# connector-top-j4-1.net
KiCad netlist of a schematic drawn in Altium Designer
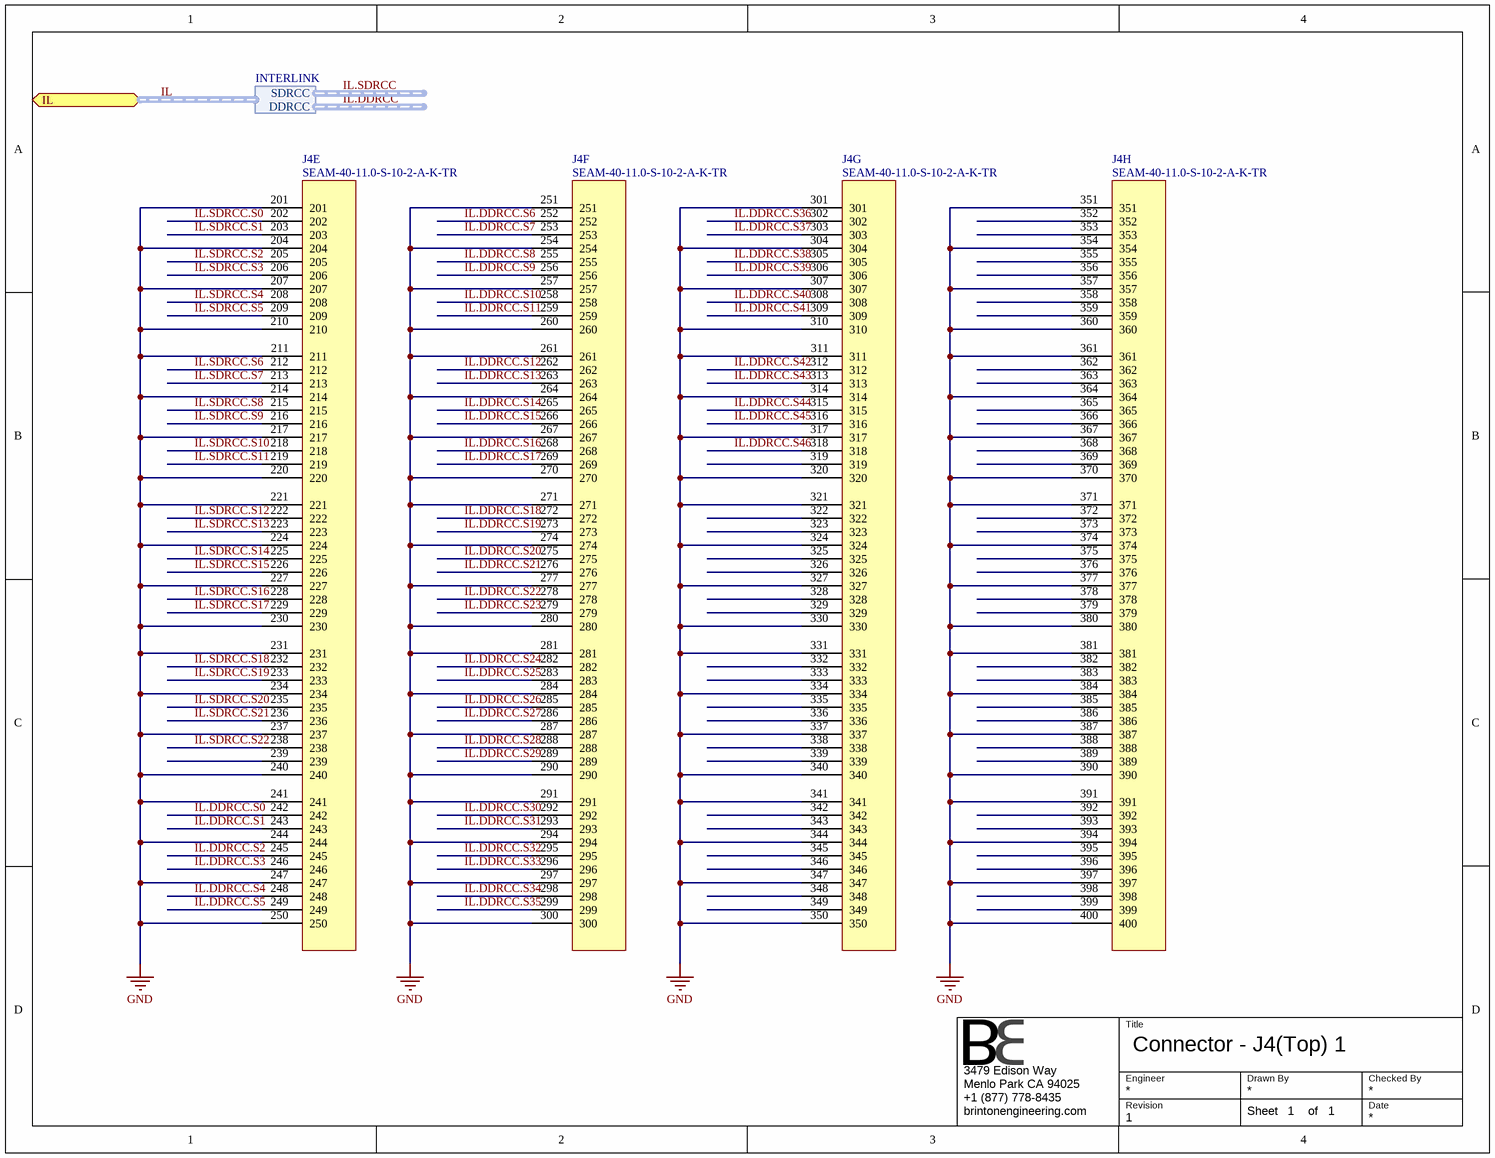
[diagram p0: connector-top-j4-1.SchDoc]

(export (version "E")
  (design (tool "Eeschema 10.0.6"))
  (components
    (comp (ref "J4")
      (value "SEAM-40-11.0-S-10-2-A-K-TR")
      (footprint "samtec:SEAM-40-11.0-S-10-2-A-K-TR")
      (description "Terminal Array Assembly, Surface Mount, 0.050\" Pitch, 400 Pins")
      (fields (field (name "MANUFACTURER") "Samtec"))
      (libsource (lib "samtec") (part "SEAM-40-11.0-S-10-2-A-K-TR"))
    )
  )
  (nets
    (net (code "3") (name "/IL.DDRCC.S0") (class "Default")
      (node (ref "J4") (pin "242") (pinfunction "242_242") (pintype "passive"))
    )
    (net (code "4") (name "/IL.DDRCC.S1") (class "Default")
      (node (ref "J4") (pin "243") (pinfunction "243_243") (pintype "passive"))
    )
    (net (code "5") (name "/IL.DDRCC.S2") (class "Default")
      (node (ref "J4") (pin "245") (pinfunction "245_245") (pintype "passive"))
    )
    (net (code "6") (name "/IL.DDRCC.S3") (class "Default")
      (node (ref "J4") (pin "246") (pinfunction "246_246") (pintype "passive"))
    )
    (net (code "7") (name "/IL.DDRCC.S4") (class "Default")
      (node (ref "J4") (pin "248") (pinfunction "248_248") (pintype "passive"))
    )
    (net (code "8") (name "/IL.DDRCC.S5") (class "Default")
      (node (ref "J4") (pin "249") (pinfunction "249_249") (pintype "passive"))
    )
    (net (code "9") (name "/IL.DDRCC.S6") (class "Default")
      (node (ref "J4") (pin "252") (pinfunction "252_252") (pintype "passive"))
    )
    (net (code "10") (name "/IL.DDRCC.S7") (class "Default")
      (node (ref "J4") (pin "253") (pinfunction "253_253") (pintype "passive"))
    )
    (net (code "11") (name "/IL.DDRCC.S8") (class "Default")
      (node (ref "J4") (pin "255") (pinfunction "255_255") (pintype "passive"))
    )
    (net (code "12") (name "/IL.DDRCC.S9") (class "Default")
      (node (ref "J4") (pin "256") (pinfunction "256_256") (pintype "passive"))
    )
    (net (code "13") (name "/IL.DDRCC.S10") (class "Default")
      (node (ref "J4") (pin "258") (pinfunction "258_258") (pintype "passive"))
    )
    (net (code "14") (name "/IL.DDRCC.S11") (class "Default")
      (node (ref "J4") (pin "259") (pinfunction "259_259") (pintype "passive"))
    )
    (net (code "15") (name "/IL.DDRCC.S12") (class "Default")
      (node (ref "J4") (pin "262") (pinfunction "262_262") (pintype "passive"))
    )
    (net (code "16") (name "/IL.DDRCC.S13") (class "Default")
      (node (ref "J4") (pin "263") (pinfunction "263_263") (pintype "passive"))
    )
    (net (code "17") (name "/IL.DDRCC.S14") (class "Default")
      (node (ref "J4") (pin "265") (pinfunction "265_265") (pintype "passive"))
    )
    (net (code "18") (name "/IL.DDRCC.S15") (class "Default")
      (node (ref "J4") (pin "266") (pinfunction "266_266") (pintype "passive"))
    )
    (net (code "19") (name "/IL.DDRCC.S16") (class "Default")
      (node (ref "J4") (pin "268") (pinfunction "268_268") (pintype "passive"))
    )
    (net (code "20") (name "/IL.DDRCC.S17") (class "Default")
      (node (ref "J4") (pin "269") (pinfunction "269_269") (pintype "passive"))
    )
    (net (code "21") (name "/IL.DDRCC.S18") (class "Default")
      (node (ref "J4") (pin "272") (pinfunction "272_272") (pintype "passive"))
    )
    (net (code "22") (name "/IL.DDRCC.S19") (class "Default")
      (node (ref "J4") (pin "273") (pinfunction "273_273") (pintype "passive"))
    )
    (net (code "23") (name "/IL.DDRCC.S20") (class "Default")
      (node (ref "J4") (pin "275") (pinfunction "275_275") (pintype "passive"))
    )
    (net (code "24") (name "/IL.DDRCC.S21") (class "Default")
      (node (ref "J4") (pin "276") (pinfunction "276_276") (pintype "passive"))
    )
    (net (code "25") (name "/IL.DDRCC.S22") (class "Default")
      (node (ref "J4") (pin "278") (pinfunction "278_278") (pintype "passive"))
    )
    (net (code "26") (name "/IL.DDRCC.S23") (class "Default")
      (node (ref "J4") (pin "279") (pinfunction "279_279") (pintype "passive"))
    )
    (net (code "27") (name "/IL.DDRCC.S24") (class "Default")
      (node (ref "J4") (pin "282") (pinfunction "282_282") (pintype "passive"))
    )
    (net (code "28") (name "/IL.DDRCC.S25") (class "Default")
      (node (ref "J4") (pin "283") (pinfunction "283_283") (pintype "passive"))
    )
    (net (code "29") (name "/IL.DDRCC.S26") (class "Default")
      (node (ref "J4") (pin "285") (pinfunction "285_285") (pintype "passive"))
    )
    (net (code "30") (name "/IL.DDRCC.S27") (class "Default")
      (node (ref "J4") (pin "286") (pinfunction "286_286") (pintype "passive"))
    )
    (net (code "31") (name "/IL.DDRCC.S28") (class "Default")
      (node (ref "J4") (pin "288") (pinfunction "288_288") (pintype "passive"))
    )
    (net (code "32") (name "/IL.DDRCC.S29") (class "Default")
      (node (ref "J4") (pin "289") (pinfunction "289_289") (pintype "passive"))
    )
    (net (code "33") (name "/IL.DDRCC.S30") (class "Default")
      (node (ref "J4") (pin "292") (pinfunction "292_292") (pintype "passive"))
    )
    (net (code "34") (name "/IL.DDRCC.S31") (class "Default")
      (node (ref "J4") (pin "293") (pinfunction "293_293") (pintype "passive"))
    )
    (net (code "35") (name "/IL.DDRCC.S32") (class "Default")
      (node (ref "J4") (pin "295") (pinfunction "295_295") (pintype "passive"))
    )
    (net (code "36") (name "/IL.DDRCC.S33") (class "Default")
      (node (ref "J4") (pin "296") (pinfunction "296_296") (pintype "passive"))
    )
    (net (code "37") (name "/IL.DDRCC.S34") (class "Default")
      (node (ref "J4") (pin "298") (pinfunction "298_298") (pintype "passive"))
    )
    (net (code "38") (name "/IL.DDRCC.S35") (class "Default")
      (node (ref "J4") (pin "299") (pinfunction "299_299") (pintype "passive"))
    )
    (net (code "39") (name "/IL.DDRCC.S36") (class "Default")
      (node (ref "J4") (pin "302") (pinfunction "302_302") (pintype "passive"))
    )
    (net (code "40") (name "/IL.DDRCC.S37") (class "Default")
      (node (ref "J4") (pin "303") (pinfunction "303_303") (pintype "passive"))
    )
    (net (code "41") (name "/IL.DDRCC.S38") (class "Default")
      (node (ref "J4") (pin "305") (pinfunction "305_305") (pintype "passive"))
    )
    (net (code "42") (name "/IL.DDRCC.S39") (class "Default")
      (node (ref "J4") (pin "306") (pinfunction "306_306") (pintype "passive"))
    )
    (net (code "43") (name "/IL.DDRCC.S40") (class "Default")
      (node (ref "J4") (pin "308") (pinfunction "308_308") (pintype "passive"))
    )
    (net (code "44") (name "/IL.DDRCC.S41") (class "Default")
      (node (ref "J4") (pin "309") (pinfunction "309_309") (pintype "passive"))
    )
    (net (code "45") (name "/IL.DDRCC.S42") (class "Default")
      (node (ref "J4") (pin "312") (pinfunction "312_312") (pintype "passive"))
    )
    (net (code "46") (name "/IL.DDRCC.S43") (class "Default")
      (node (ref "J4") (pin "313") (pinfunction "313_313") (pintype "passive"))
    )
    (net (code "47") (name "/IL.DDRCC.S44") (class "Default")
      (node (ref "J4") (pin "315") (pinfunction "315_315") (pintype "passive"))
    )
    (net (code "48") (name "/IL.DDRCC.S45") (class "Default")
      (node (ref "J4") (pin "316") (pinfunction "316_316") (pintype "passive"))
    )
    (net (code "49") (name "/IL.DDRCC.S46") (class "Default")
      (node (ref "J4") (pin "318") (pinfunction "318_318") (pintype "passive"))
    )
    (net (code "51") (name "/IL.SDRCC.S0") (class "Default")
      (node (ref "J4") (pin "202") (pinfunction "202_202") (pintype "passive"))
    )
    (net (code "52") (name "/IL.SDRCC.S1") (class "Default")
      (node (ref "J4") (pin "203") (pinfunction "203_203") (pintype "passive"))
    )
    (net (code "53") (name "/IL.SDRCC.S2") (class "Default")
      (node (ref "J4") (pin "205") (pinfunction "205_205") (pintype "passive"))
    )
    (net (code "54") (name "/IL.SDRCC.S3") (class "Default")
      (node (ref "J4") (pin "206") (pinfunction "206_206") (pintype "passive"))
    )
    (net (code "55") (name "/IL.SDRCC.S4") (class "Default")
      (node (ref "J4") (pin "208") (pinfunction "208_208") (pintype "passive"))
    )
    (net (code "56") (name "/IL.SDRCC.S5") (class "Default")
      (node (ref "J4") (pin "209") (pinfunction "209_209") (pintype "passive"))
    )
    (net (code "57") (name "/IL.SDRCC.S6") (class "Default")
      (node (ref "J4") (pin "212") (pinfunction "212_212") (pintype "passive"))
    )
    (net (code "58") (name "/IL.SDRCC.S7") (class "Default")
      (node (ref "J4") (pin "213") (pinfunction "213_213") (pintype "passive"))
    )
    (net (code "59") (name "/IL.SDRCC.S8") (class "Default")
      (node (ref "J4") (pin "215") (pinfunction "215_215") (pintype "passive"))
    )
    (net (code "60") (name "/IL.SDRCC.S9") (class "Default")
      (node (ref "J4") (pin "216") (pinfunction "216_216") (pintype "passive"))
    )
    (net (code "61") (name "/IL.SDRCC.S10") (class "Default")
      (node (ref "J4") (pin "218") (pinfunction "218_218") (pintype "passive"))
    )
    (net (code "62") (name "/IL.SDRCC.S11") (class "Default")
      (node (ref "J4") (pin "219") (pinfunction "219_219") (pintype "passive"))
    )
    (net (code "63") (name "/IL.SDRCC.S12") (class "Default")
      (node (ref "J4") (pin "222") (pinfunction "222_222") (pintype "passive"))
    )
    (net (code "64") (name "/IL.SDRCC.S13") (class "Default")
      (node (ref "J4") (pin "223") (pinfunction "223_223") (pintype "passive"))
    )
    (net (code "65") (name "/IL.SDRCC.S14") (class "Default")
      (node (ref "J4") (pin "225") (pinfunction "225_225") (pintype "passive"))
    )
    (net (code "66") (name "/IL.SDRCC.S15") (class "Default")
      (node (ref "J4") (pin "226") (pinfunction "226_226") (pintype "passive"))
    )
    (net (code "67") (name "/IL.SDRCC.S16") (class "Default")
      (node (ref "J4") (pin "228") (pinfunction "228_228") (pintype "passive"))
    )
    (net (code "68") (name "/IL.SDRCC.S17") (class "Default")
      (node (ref "J4") (pin "229") (pinfunction "229_229") (pintype "passive"))
    )
    (net (code "69") (name "/IL.SDRCC.S18") (class "Default")
      (node (ref "J4") (pin "232") (pinfunction "232_232") (pintype "passive"))
    )
    (net (code "70") (name "/IL.SDRCC.S19") (class "Default")
      (node (ref "J4") (pin "233") (pinfunction "233_233") (pintype "passive"))
    )
    (net (code "71") (name "/IL.SDRCC.S20") (class "Default")
      (node (ref "J4") (pin "235") (pinfunction "235_235") (pintype "passive"))
    )
    (net (code "72") (name "/IL.SDRCC.S21") (class "Default")
      (node (ref "J4") (pin "236") (pinfunction "236_236") (pintype "passive"))
    )
    (net (code "73") (name "/IL.SDRCC.S22") (class "Default")
      (node (ref "J4") (pin "238") (pinfunction "238_238") (pintype "passive"))
    )
    (net (code "75") (name "GND") (class "Default")
      (node (ref "J4") (pin "201") (pinfunction "201_201") (pintype "passive"))
      (node (ref "J4") (pin "204") (pinfunction "204_204") (pintype "passive"))
      (node (ref "J4") (pin "207") (pinfunction "207_207") (pintype "passive"))
      (node (ref "J4") (pin "210") (pinfunction "210_210") (pintype "passive"))
      (node (ref "J4") (pin "211") (pinfunction "211_211") (pintype "passive"))
      (node (ref "J4") (pin "214") (pinfunction "214_214") (pintype "passive"))
      (node (ref "J4") (pin "217") (pinfunction "217_217") (pintype "passive"))
      (node (ref "J4") (pin "220") (pinfunction "220_220") (pintype "passive"))
      (node (ref "J4") (pin "221") (pinfunction "221_221") (pintype "passive"))
      (node (ref "J4") (pin "224") (pinfunction "224_224") (pintype "passive"))
      (node (ref "J4") (pin "227") (pinfunction "227_227") (pintype "passive"))
      (node (ref "J4") (pin "230") (pinfunction "230_230") (pintype "passive"))
      (node (ref "J4") (pin "231") (pinfunction "231_231") (pintype "passive"))
      (node (ref "J4") (pin "234") (pinfunction "234_234") (pintype "passive"))
      (node (ref "J4") (pin "237") (pinfunction "237_237") (pintype "passive"))
      (node (ref "J4") (pin "240") (pinfunction "240_240") (pintype "passive"))
      (node (ref "J4") (pin "241") (pinfunction "241_241") (pintype "passive"))
      (node (ref "J4") (pin "244") (pinfunction "244_244") (pintype "passive"))
      (node (ref "J4") (pin "247") (pinfunction "247_247") (pintype "passive"))
      (node (ref "J4") (pin "250") (pinfunction "250_250") (pintype "passive"))
      (node (ref "J4") (pin "251") (pinfunction "251_251") (pintype "passive"))
      (node (ref "J4") (pin "254") (pinfunction "254_254") (pintype "passive"))
      (node (ref "J4") (pin "257") (pinfunction "257_257") (pintype "passive"))
      (node (ref "J4") (pin "260") (pinfunction "260_260") (pintype "passive"))
      (node (ref "J4") (pin "261") (pinfunction "261_261") (pintype "passive"))
      (node (ref "J4") (pin "264") (pinfunction "264_264") (pintype "passive"))
      (node (ref "J4") (pin "267") (pinfunction "267_267") (pintype "passive"))
      (node (ref "J4") (pin "270") (pinfunction "270_270") (pintype "passive"))
      (node (ref "J4") (pin "271") (pinfunction "271_271") (pintype "passive"))
      (node (ref "J4") (pin "274") (pinfunction "274_274") (pintype "passive"))
      (node (ref "J4") (pin "277") (pinfunction "277_277") (pintype "passive"))
      (node (ref "J4") (pin "280") (pinfunction "280_280") (pintype "passive"))
      (node (ref "J4") (pin "281") (pinfunction "281_281") (pintype "passive"))
      (node (ref "J4") (pin "284") (pinfunction "284_284") (pintype "passive"))
      (node (ref "J4") (pin "287") (pinfunction "287_287") (pintype "passive"))
      (node (ref "J4") (pin "290") (pinfunction "290_290") (pintype "passive"))
      (node (ref "J4") (pin "291") (pinfunction "291_291") (pintype "passive"))
      (node (ref "J4") (pin "294") (pinfunction "294_294") (pintype "passive"))
      (node (ref "J4") (pin "297") (pinfunction "297_297") (pintype "passive"))
      (node (ref "J4") (pin "300") (pinfunction "300_300") (pintype "passive"))
      (node (ref "J4") (pin "301") (pinfunction "301_301") (pintype "passive"))
      (node (ref "J4") (pin "304") (pinfunction "304_304") (pintype "passive"))
      (node (ref "J4") (pin "307") (pinfunction "307_307") (pintype "passive"))
      (node (ref "J4") (pin "310") (pinfunction "310_310") (pintype "passive"))
      (node (ref "J4") (pin "311") (pinfunction "311_311") (pintype "passive"))
      (node (ref "J4") (pin "314") (pinfunction "314_314") (pintype "passive"))
      (node (ref "J4") (pin "317") (pinfunction "317_317") (pintype "passive"))
      (node (ref "J4") (pin "320") (pinfunction "320_320") (pintype "passive"))
      (node (ref "J4") (pin "321") (pinfunction "321_321") (pintype "passive"))
      (node (ref "J4") (pin "324") (pinfunction "324_324") (pintype "passive"))
      (node (ref "J4") (pin "327") (pinfunction "327_327") (pintype "passive"))
      (node (ref "J4") (pin "330") (pinfunction "330_330") (pintype "passive"))
      (node (ref "J4") (pin "331") (pinfunction "331_331") (pintype "passive"))
      (node (ref "J4") (pin "334") (pinfunction "334_334") (pintype "passive"))
      (node (ref "J4") (pin "337") (pinfunction "337_337") (pintype "passive"))
      (node (ref "J4") (pin "340") (pinfunction "340_340") (pintype "passive"))
      (node (ref "J4") (pin "341") (pinfunction "341_341") (pintype "passive"))
      (node (ref "J4") (pin "344") (pinfunction "344_344") (pintype "passive"))
      (node (ref "J4") (pin "347") (pinfunction "347_347") (pintype "passive"))
      (node (ref "J4") (pin "350") (pinfunction "350_350") (pintype "passive"))
      (node (ref "J4") (pin "351") (pinfunction "351_351") (pintype "passive"))
      (node (ref "J4") (pin "354") (pinfunction "354_354") (pintype "passive"))
      (node (ref "J4") (pin "357") (pinfunction "357_357") (pintype "passive"))
      (node (ref "J4") (pin "360") (pinfunction "360_360") (pintype "passive"))
      (node (ref "J4") (pin "361") (pinfunction "361_361") (pintype "passive"))
      (node (ref "J4") (pin "364") (pinfunction "364_364") (pintype "passive"))
      (node (ref "J4") (pin "367") (pinfunction "367_367") (pintype "passive"))
      (node (ref "J4") (pin "370") (pinfunction "370_370") (pintype "passive"))
      (node (ref "J4") (pin "371") (pinfunction "371_371") (pintype "passive"))
      (node (ref "J4") (pin "374") (pinfunction "374_374") (pintype "passive"))
      (node (ref "J4") (pin "377") (pinfunction "377_377") (pintype "passive"))
      (node (ref "J4") (pin "380") (pinfunction "380_380") (pintype "passive"))
      (node (ref "J4") (pin "381") (pinfunction "381_381") (pintype "passive"))
      (node (ref "J4") (pin "384") (pinfunction "384_384") (pintype "passive"))
      (node (ref "J4") (pin "387") (pinfunction "387_387") (pintype "passive"))
      (node (ref "J4") (pin "390") (pinfunction "390_390") (pintype "passive"))
      (node (ref "J4") (pin "391") (pinfunction "391_391") (pintype "passive"))
      (node (ref "J4") (pin "394") (pinfunction "394_394") (pintype "passive"))
      (node (ref "J4") (pin "397") (pinfunction "397_397") (pintype "passive"))
      (node (ref "J4") (pin "400") (pinfunction "400_400") (pintype "passive"))
    )
    (net (code "76") (name "unconnected-(J4-Pad239)") (class "Default")
      (node (ref "J4") (pin "239") (pinfunction "239_239") (pintype "passive"))
    )
    (net (code "77") (name "unconnected-(J4-Pad319)") (class "Default")
      (node (ref "J4") (pin "319") (pinfunction "319_319") (pintype "passive"))
    )
    (net (code "78") (name "unconnected-(J4-Pad322)") (class "Default")
      (node (ref "J4") (pin "322") (pinfunction "322_322") (pintype "passive"))
    )
    (net (code "79") (name "unconnected-(J4-Pad323)") (class "Default")
      (node (ref "J4") (pin "323") (pinfunction "323_323") (pintype "passive"))
    )
    (net (code "80") (name "unconnected-(J4-Pad325)") (class "Default")
      (node (ref "J4") (pin "325") (pinfunction "325_325") (pintype "passive"))
    )
    (net (code "81") (name "unconnected-(J4-Pad326)") (class "Default")
      (node (ref "J4") (pin "326") (pinfunction "326_326") (pintype "passive"))
    )
    (net (code "82") (name "unconnected-(J4-Pad328)") (class "Default")
      (node (ref "J4") (pin "328") (pinfunction "328_328") (pintype "passive"))
    )
    (net (code "83") (name "unconnected-(J4-Pad329)") (class "Default")
      (node (ref "J4") (pin "329") (pinfunction "329_329") (pintype "passive"))
    )
    (net (code "84") (name "unconnected-(J4-Pad332)") (class "Default")
      (node (ref "J4") (pin "332") (pinfunction "332_332") (pintype "passive"))
    )
    (net (code "85") (name "unconnected-(J4-Pad333)") (class "Default")
      (node (ref "J4") (pin "333") (pinfunction "333_333") (pintype "passive"))
    )
    (net (code "86") (name "unconnected-(J4-Pad335)") (class "Default")
      (node (ref "J4") (pin "335") (pinfunction "335_335") (pintype "passive"))
    )
    (net (code "87") (name "unconnected-(J4-Pad336)") (class "Default")
      (node (ref "J4") (pin "336") (pinfunction "336_336") (pintype "passive"))
    )
    (net (code "88") (name "unconnected-(J4-Pad338)") (class "Default")
      (node (ref "J4") (pin "338") (pinfunction "338_338") (pintype "passive"))
    )
    (net (code "89") (name "unconnected-(J4-Pad339)") (class "Default")
      (node (ref "J4") (pin "339") (pinfunction "339_339") (pintype "passive"))
    )
    (net (code "90") (name "unconnected-(J4-Pad342)") (class "Default")
      (node (ref "J4") (pin "342") (pinfunction "342_342") (pintype "passive"))
    )
    (net (code "91") (name "unconnected-(J4-Pad343)") (class "Default")
      (node (ref "J4") (pin "343") (pinfunction "343_343") (pintype "passive"))
    )
    (net (code "92") (name "unconnected-(J4-Pad345)") (class "Default")
      (node (ref "J4") (pin "345") (pinfunction "345_345") (pintype "passive"))
    )
    (net (code "93") (name "unconnected-(J4-Pad346)") (class "Default")
      (node (ref "J4") (pin "346") (pinfunction "346_346") (pintype "passive"))
    )
    (net (code "94") (name "unconnected-(J4-Pad348)") (class "Default")
      (node (ref "J4") (pin "348") (pinfunction "348_348") (pintype "passive"))
    )
    (net (code "95") (name "unconnected-(J4-Pad349)") (class "Default")
      (node (ref "J4") (pin "349") (pinfunction "349_349") (pintype "passive"))
    )
    (net (code "96") (name "unconnected-(J4-Pad352)") (class "Default")
      (node (ref "J4") (pin "352") (pinfunction "352_352") (pintype "passive"))
    )
    (net (code "97") (name "unconnected-(J4-Pad353)") (class "Default")
      (node (ref "J4") (pin "353") (pinfunction "353_353") (pintype "passive"))
    )
    (net (code "98") (name "unconnected-(J4-Pad355)") (class "Default")
      (node (ref "J4") (pin "355") (pinfunction "355_355") (pintype "passive"))
    )
    (net (code "99") (name "unconnected-(J4-Pad356)") (class "Default")
      (node (ref "J4") (pin "356") (pinfunction "356_356") (pintype "passive"))
    )
    (net (code "100") (name "unconnected-(J4-Pad358)") (class "Default")
      (node (ref "J4") (pin "358") (pinfunction "358_358") (pintype "passive"))
    )
    (net (code "101") (name "unconnected-(J4-Pad359)") (class "Default")
      (node (ref "J4") (pin "359") (pinfunction "359_359") (pintype "passive"))
    )
    (net (code "102") (name "unconnected-(J4-Pad362)") (class "Default")
      (node (ref "J4") (pin "362") (pinfunction "362_362") (pintype "passive"))
    )
    (net (code "103") (name "unconnected-(J4-Pad363)") (class "Default")
      (node (ref "J4") (pin "363") (pinfunction "363_363") (pintype "passive"))
    )
    (net (code "104") (name "unconnected-(J4-Pad365)") (class "Default")
      (node (ref "J4") (pin "365") (pinfunction "365_365") (pintype "passive"))
    )
    (net (code "105") (name "unconnected-(J4-Pad366)") (class "Default")
      (node (ref "J4") (pin "366") (pinfunction "366_366") (pintype "passive"))
    )
    (net (code "106") (name "unconnected-(J4-Pad368)") (class "Default")
      (node (ref "J4") (pin "368") (pinfunction "368_368") (pintype "passive"))
    )
    (net (code "107") (name "unconnected-(J4-Pad369)") (class "Default")
      (node (ref "J4") (pin "369") (pinfunction "369_369") (pintype "passive"))
    )
    (net (code "108") (name "unconnected-(J4-Pad372)") (class "Default")
      (node (ref "J4") (pin "372") (pinfunction "372_372") (pintype "passive"))
    )
    (net (code "109") (name "unconnected-(J4-Pad373)") (class "Default")
      (node (ref "J4") (pin "373") (pinfunction "373_373") (pintype "passive"))
    )
    (net (code "110") (name "unconnected-(J4-Pad375)") (class "Default")
      (node (ref "J4") (pin "375") (pinfunction "375_375") (pintype "passive"))
    )
    (net (code "111") (name "unconnected-(J4-Pad376)") (class "Default")
      (node (ref "J4") (pin "376") (pinfunction "376_376") (pintype "passive"))
    )
    (net (code "112") (name "unconnected-(J4-Pad378)") (class "Default")
      (node (ref "J4") (pin "378") (pinfunction "378_378") (pintype "passive"))
    )
    (net (code "113") (name "unconnected-(J4-Pad379)") (class "Default")
      (node (ref "J4") (pin "379") (pinfunction "379_379") (pintype "passive"))
    )
    (net (code "114") (name "unconnected-(J4-Pad382)") (class "Default")
      (node (ref "J4") (pin "382") (pinfunction "382_382") (pintype "passive"))
    )
    (net (code "115") (name "unconnected-(J4-Pad383)") (class "Default")
      (node (ref "J4") (pin "383") (pinfunction "383_383") (pintype "passive"))
    )
    (net (code "116") (name "unconnected-(J4-Pad385)") (class "Default")
      (node (ref "J4") (pin "385") (pinfunction "385_385") (pintype "passive"))
    )
    (net (code "117") (name "unconnected-(J4-Pad386)") (class "Default")
      (node (ref "J4") (pin "386") (pinfunction "386_386") (pintype "passive"))
    )
    (net (code "118") (name "unconnected-(J4-Pad388)") (class "Default")
      (node (ref "J4") (pin "388") (pinfunction "388_388") (pintype "passive"))
    )
    (net (code "119") (name "unconnected-(J4-Pad389)") (class "Default")
      (node (ref "J4") (pin "389") (pinfunction "389_389") (pintype "passive"))
    )
    (net (code "120") (name "unconnected-(J4-Pad392)") (class "Default")
      (node (ref "J4") (pin "392") (pinfunction "392_392") (pintype "passive"))
    )
    (net (code "121") (name "unconnected-(J4-Pad393)") (class "Default")
      (node (ref "J4") (pin "393") (pinfunction "393_393") (pintype "passive"))
    )
    (net (code "122") (name "unconnected-(J4-Pad395)") (class "Default")
      (node (ref "J4") (pin "395") (pinfunction "395_395") (pintype "passive"))
    )
    (net (code "123") (name "unconnected-(J4-Pad396)") (class "Default")
      (node (ref "J4") (pin "396") (pinfunction "396_396") (pintype "passive"))
    )
    (net (code "124") (name "unconnected-(J4-Pad398)") (class "Default")
      (node (ref "J4") (pin "398") (pinfunction "398_398") (pintype "passive"))
    )
    (net (code "125") (name "unconnected-(J4-Pad399)") (class "Default")
      (node (ref "J4") (pin "399") (pinfunction "399_399") (pintype "passive"))
    )
  )
)
